# proyek_kelompok_10.net
KiCad netlist of a schematic drawn in EAGLE
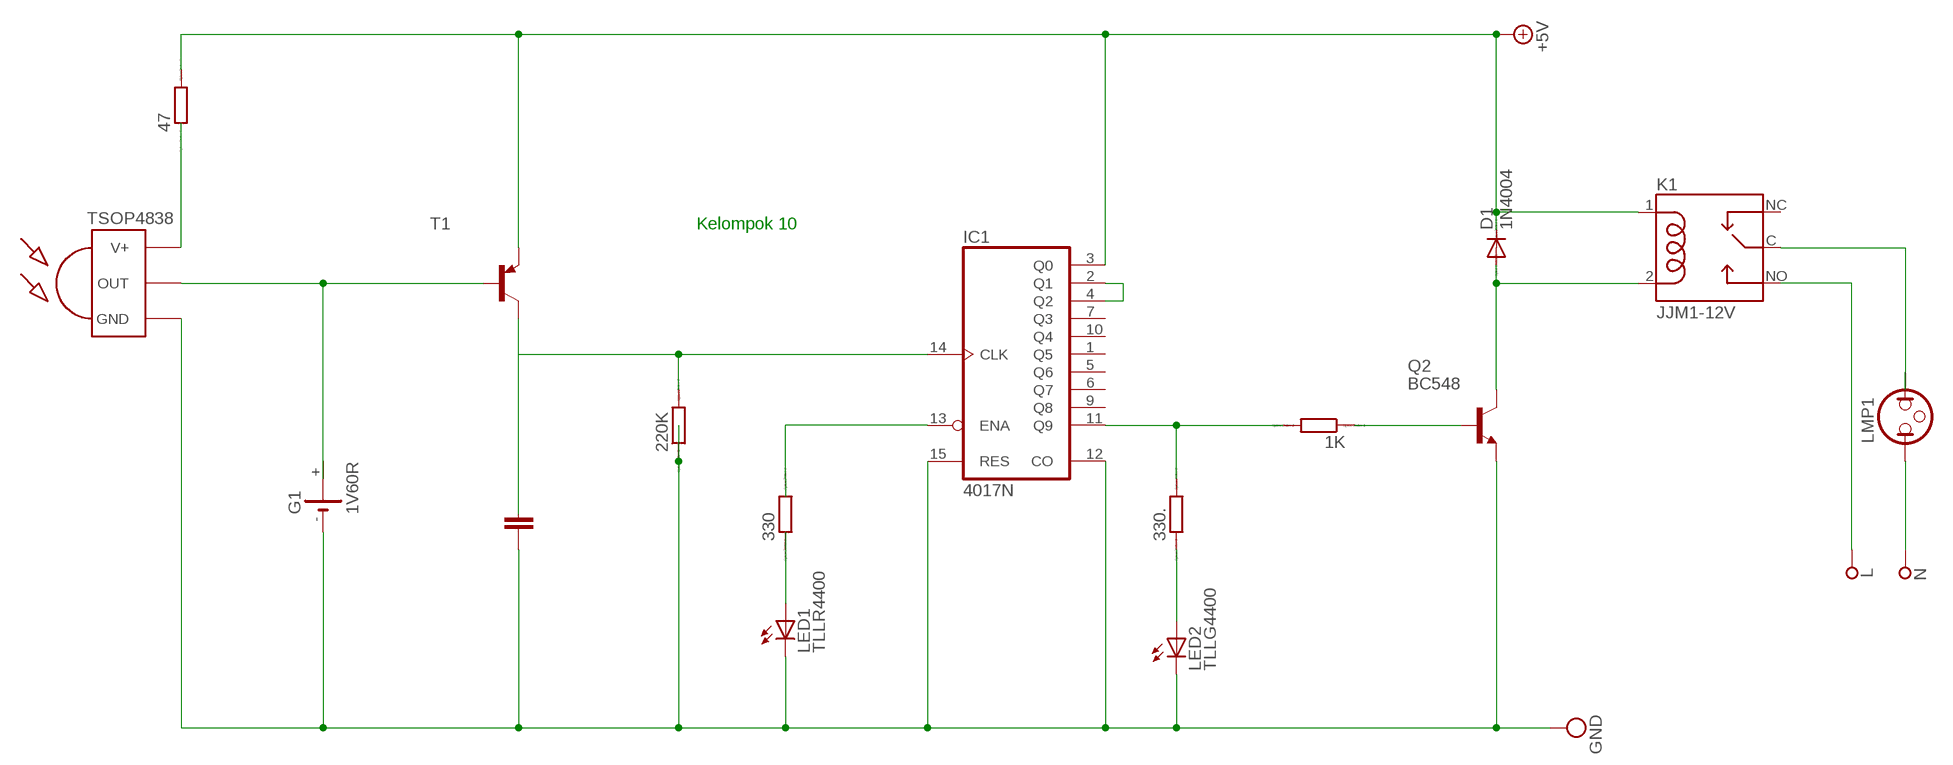
[diagram p0: schematic, sheet 1]

(export (version "E")
  (design (tool "Eeschema 10.0.6"))
  (components
    (comp (ref "1K")
      (value "R0207/10")
      (footprint "eagle-import:0207_10")
      (libsource (lib "eagle-import") (part "R0207/10"))
    )
    (comp (ref "47")
      (value "R0207/10")
      (footprint "eagle-import:0207_10")
      (libsource (lib "eagle-import") (part "R0207/10"))
    )
    (comp (ref "220K")
      (value "R0207/10")
      (footprint "eagle-import:0207_10")
      (libsource (lib "eagle-import") (part "R0207/10"))
    )
    (comp (ref "330")
      (value "R0207/10")
      (footprint "eagle-import:0207_10")
      (libsource (lib "eagle-import") (part "R0207/10"))
    )
    (comp (ref "330.")
      (value "R0207/10")
      (footprint "eagle-import:0207_10")
      (libsource (lib "eagle-import") (part "R0207/10"))
    )
    (comp (ref "D1")
      (value "1N4004")
      (footprint "eagle-import:DO41-10")
      (libsource (lib "eagle-import") (part "1N4004"))
    )
    (comp (ref "G1")
      (value "1V60R")
      (footprint "eagle-import:1V60R")
      (libsource (lib "eagle-import") (part "1V60R"))
    )
    (comp (ref "IC1")
      (value "4017N")
      (footprint "eagle-import:DIL16")
      (libsource (lib "eagle-import") (part "4017N"))
    )
    (comp (ref "K1")
      (value "JJM1-12V")
      (footprint "eagle-import:RELAY_JJM1-12V")
      (fields (field (name "MF") "Panasonic Electric Works"))
      (libsource (lib "eagle-import") (part "JJM1-12V"))
    )
    (comp (ref "L")
      (value "SPECIAL_DRILL_0.1000")
      (footprint "eagle-import:PAD_0.1000")
      (libsource (lib "eagle-import") (part "SPECIAL_DRILL_0.1000"))
    )
    (comp (ref "LED1")
      (value "TLLR4400")
      (footprint "eagle-import:LED3MM")
      (fields (field (name "MF") "VISHAY SEMICONDUCTOR"))
      (libsource (lib "eagle-import") (part "TLLR4400"))
    )
    (comp (ref "LED2")
      (value "TLLG4400")
      (footprint "eagle-import:LED3MM")
      (fields (field (name "MF") "VISHAY SEMICONDUCTOR"))
      (libsource (lib "eagle-import") (part "TLLG4400"))
    )
    (comp (ref "LMP1")
      (value "NEON")
      (footprint "eagle-import:LDH-3R")
      (libsource (lib "eagle-import") (part "NEON"))
    )
    (comp (ref "N")
      (value "SPECIAL_DRILL_0.1000")
      (footprint "eagle-import:PAD_0.1000")
      (libsource (lib "eagle-import") (part "SPECIAL_DRILL_0.1000"))
    )
    (comp (ref "Q2")
      (value "BC548")
      (footprint "eagle-import:TO92-EBC")
      (libsource (lib "eagle-import") (part "BC548"))
    )
    (comp (ref "T1")
      (value "BC558A-PNP-TO92-EBC")
      (footprint "eagle-import:TO92-EBC")
      (libsource (lib "eagle-import") (part "-PNP-TO92-EBCBC558A"))
    )
    (comp (ref "U$1")
      (value "TSOP4838")
      (footprint "eagle-import:TSOP18XX")
      (libsource (lib "eagle-import") (part "TSOP4838"))
    )
  )
  (nets
    (net (code "1") (name "+5V") (class "Default")
      (node (ref "47") (pin "2") (pinfunction "2_2") (pintype "passive"))
      (node (ref "D1") (pin "C") (pinfunction "C_C") (pintype "passive"))
      (node (ref "IC1") (pin "3") (pinfunction "Q0_3") (pintype "output"))
      (node (ref "K1") (pin "1") (pinfunction "C1_1") (pintype "passive"))
      (node (ref "T1") (pin "E") (pinfunction "E_E") (pintype "passive"))
    )
    (net (code "2") (name "GND") (class "Default")
      (node (ref "220K") (pin "1") (pinfunction "1_1") (pintype "passive"))
      (node (ref "G1") (pin "-") (pinfunction "-_-") (pintype "passive"))
      (node (ref "IC1") (pin "12") (pinfunction "CO_12") (pintype "output"))
      (node (ref "IC1") (pin "15") (pinfunction "RES_15") (pintype "input"))
      (node (ref "LED1") (pin "K") (pinfunction "C_K") (pintype "passive"))
      (node (ref "LED2") (pin "K") (pinfunction "C_K") (pintype "passive"))
      (node (ref "Q2") (pin "E") (pinfunction "E_E") (pintype "passive"))
      (node (ref "U$1") (pin "GND") (pinfunction "GND_GND") (pintype "bidirectional"))
    )
    (net (code "3") (name "Net-(1K-Pad1)") (class "Default")
      (node (ref "1K") (pin "1") (pinfunction "1_1") (pintype "passive"))
      (node (ref "Q2") (pin "B") (pinfunction "B_B") (pintype "passive"))
    )
    (net (code "4") (name "Net-(330-Pad1)") (class "Default")
      (node (ref "330") (pin "1") (pinfunction "1_1") (pintype "passive"))
      (node (ref "LED1") (pin "A") (pinfunction "A_A") (pintype "passive"))
    )
    (net (code "5") (name "Net-(330.-Pad1)") (class "Default")
      (node (ref "330.") (pin "1") (pinfunction "1_1") (pintype "passive"))
      (node (ref "LED2") (pin "A") (pinfunction "A_A") (pintype "passive"))
    )
    (net (code "6") (name "Net-(G1-+-Pad+@1)") (class "Default")
      (node (ref "G1") (pin "+@1") (pinfunction "+_+@1") (pintype "passive"))
      (node (ref "T1") (pin "B") (pinfunction "B_B") (pintype "passive"))
      (node (ref "U$1") (pin "OUT") (pinfunction "OUT_OUT") (pintype "bidirectional"))
    )
    (net (code "7") (name "Net-(IC1A-CLK)") (class "Default")
      (node (ref "220K") (pin "2") (pinfunction "2_2") (pintype "passive"))
      (node (ref "IC1") (pin "14") (pinfunction "CLK_14") (pintype "input"))
    )
    (net (code "8") (name "Net-(IC1A-ENA)") (class "Default")
      (node (ref "330") (pin "2") (pinfunction "2_2") (pintype "passive"))
      (node (ref "IC1") (pin "13") (pinfunction "ENA_13") (pintype "input"))
    )
    (net (code "9") (name "Net-(IC1A-Q1)") (class "Default")
      (node (ref "IC1") (pin "2") (pinfunction "Q1_2") (pintype "output"))
      (node (ref "IC1") (pin "4") (pinfunction "Q2_4") (pintype "output"))
    )
    (net (code "10") (name "Net-(IC1A-Q9)") (class "Default")
      (node (ref "1K") (pin "2") (pinfunction "2_2") (pintype "passive"))
      (node (ref "330.") (pin "2") (pinfunction "2_2") (pintype "passive"))
      (node (ref "IC1") (pin "11") (pinfunction "Q9_11") (pintype "output"))
    )
    (net (code "11") (name "Net-(K1-C2)") (class "Default")
      (node (ref "D1") (pin "A") (pinfunction "A_A") (pintype "passive"))
      (node (ref "K1") (pin "2") (pinfunction "C2_2") (pintype "passive"))
      (node (ref "Q2") (pin "C") (pinfunction "C_C") (pintype "passive"))
    )
    (net (code "12") (name "Net-(K1-M)") (class "Default")
      (node (ref "K1") (pin "C") (pinfunction "M_C") (pintype "passive"))
      (node (ref "LMP1") (pin "2") (pinfunction "2_2") (pintype "passive"))
    )
    (net (code "13") (name "Net-(K1-PadNO)") (class "Default")
      (node (ref "K1") (pin "NO") (pinfunction "NO_NO") (pintype "passive"))
      (node (ref "L") (pin "1") (pinfunction "1_1") (pintype "passive"))
    )
    (net (code "14") (name "Net-(LMP1-Pad1)") (class "Default")
      (node (ref "LMP1") (pin "1") (pinfunction "1_1") (pintype "passive"))
      (node (ref "N") (pin "1") (pinfunction "1_1") (pintype "passive"))
    )
    (net (code "15") (name "Net-(U$1-V+)") (class "Default")
      (node (ref "47") (pin "1") (pinfunction "1_1") (pintype "passive"))
      (node (ref "U$1") (pin "VCC") (pinfunction "V+_VCC") (pintype "bidirectional"))
    )
    (net (code "16") (name "unconnected-(G1-Pad+)") (class "Default")
      (node (ref "G1") (pin "+") (pinfunction "+_+") (pintype "passive"))
    )
    (net (code "17") (name "unconnected-(IC1A-Q3-Pad7)") (class "Default")
      (node (ref "IC1") (pin "7") (pinfunction "Q3_7") (pintype "output"))
    )
    (net (code "18") (name "unconnected-(IC1A-Q4-Pad10)") (class "Default")
      (node (ref "IC1") (pin "10") (pinfunction "Q4_10") (pintype "output"))
    )
    (net (code "19") (name "unconnected-(IC1A-Q5-Pad1)") (class "Default")
      (node (ref "IC1") (pin "1") (pinfunction "Q5_1") (pintype "output"))
    )
    (net (code "20") (name "unconnected-(IC1A-Q6-Pad5)") (class "Default")
      (node (ref "IC1") (pin "5") (pinfunction "Q6_5") (pintype "output"))
    )
    (net (code "21") (name "unconnected-(IC1A-Q7-Pad6)") (class "Default")
      (node (ref "IC1") (pin "6") (pinfunction "Q7_6") (pintype "output"))
    )
    (net (code "22") (name "unconnected-(IC1A-Q8-Pad9)") (class "Default")
      (node (ref "IC1") (pin "9") (pinfunction "Q8_9") (pintype "output"))
    )
    (net (code "23") (name "unconnected-(K1-PadNC)") (class "Default")
      (node (ref "K1") (pin "NC") (pinfunction "NC_NC") (pintype "passive"))
    )
    (net (code "24") (name "unconnected-(T1-PadC)") (class "Default")
      (node (ref "T1") (pin "C") (pinfunction "C_C") (pintype "passive"))
    )
  )
)
